# Loguino_mini_v1_2.net
KiCad netlist of a schematic drawn in EAGLE
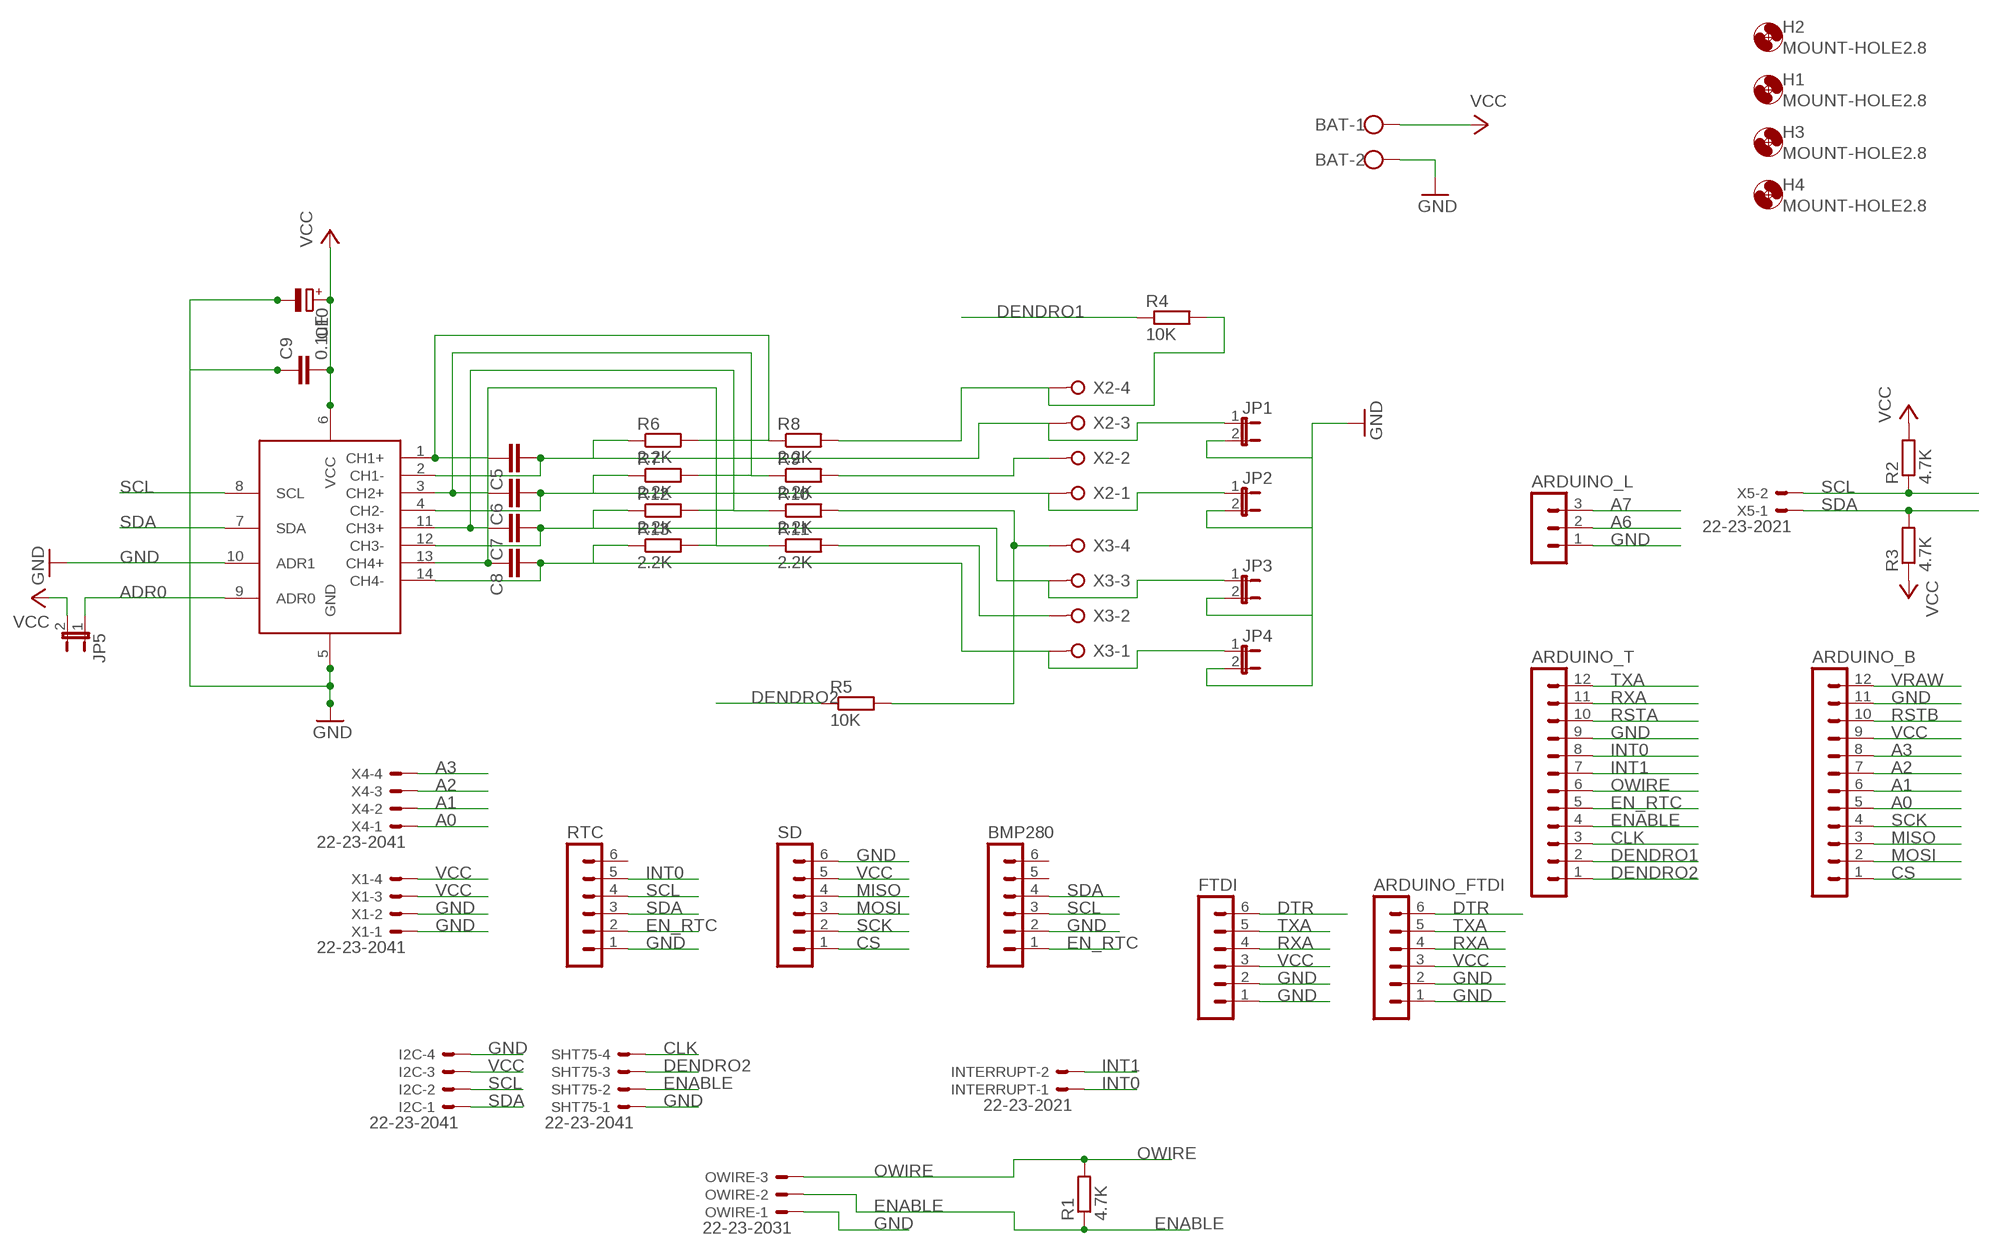
[diagram p0: schematic, sheet 1]

(export (version "E")
  (design (tool "Eeschema 10.0.6"))
  (components
    (comp (ref "ARDUINO_B")
      (value "MA12-1")
      (footprint "eagle-import:MA12-1")
      (libsource (lib "eagle-import") (part "MA12-1"))
    )
    (comp (ref "ARDUINO_FTDI")
      (value "MA06-1")
      (footprint "eagle-import:MA06-1")
      (libsource (lib "eagle-import") (part "MA06-1"))
    )
    (comp (ref "ARDUINO_L")
      (value "MA03-1")
      (footprint "eagle-import:MA03-1")
      (libsource (lib "eagle-import") (part "MA03-1"))
    )
    (comp (ref "ARDUINO_T")
      (value "MA12-1")
      (footprint "eagle-import:MA12-1")
      (libsource (lib "eagle-import") (part "MA12-1"))
    )
    (comp (ref "BAT")
      (value "W237-102")
      (footprint "eagle-import:W237-102")
      (fields (field (name "MPN") "237-102"))
      (libsource (lib "eagle-import") (part "W237-102"))
    )
    (comp (ref "BMP280")
      (value "MA06-1")
      (footprint "eagle-import:MA06-1")
      (libsource (lib "eagle-import") (part "MA06-1"))
    )
    (comp (ref "C5")
      (value "C-EU025-024X044")
      (footprint "eagle-import:C025-024X044")
      (libsource (lib "eagle-import") (part "C-EU025-024X044"))
    )
    (comp (ref "C6")
      (value "C-EU025-024X044")
      (footprint "eagle-import:C025-024X044")
      (libsource (lib "eagle-import") (part "C-EU025-024X044"))
    )
    (comp (ref "C7")
      (value "C-EU025-024X044")
      (footprint "eagle-import:C025-024X044")
      (libsource (lib "eagle-import") (part "C-EU025-024X044"))
    )
    (comp (ref "C8")
      (value "C-EU025-024X044")
      (footprint "eagle-import:C025-024X044")
      (libsource (lib "eagle-import") (part "C-EU025-024X044"))
    )
    (comp (ref "C9")
      (value "0.1uF")
      (footprint "eagle-import:C050-025X075")
      (libsource (lib "eagle-import") (part "C-EU050-025X075"))
    )
    (comp (ref "C10")
      (value "CPOL-EUE2,5-6E")
      (footprint "eagle-import:E2,5-6E")
      (libsource (lib "eagle-import") (part "CPOL-EUE2,5-6E"))
    )
    (comp (ref "FTDI")
      (value "MA06-1")
      (footprint "eagle-import:MA06-1")
      (libsource (lib "eagle-import") (part "MA06-1"))
    )
    (comp (ref "H1")
      (value "MOUNT-HOLE2.8")
      (footprint "eagle-import:2,8")
      (libsource (lib "eagle-import") (part "MOUNT-HOLE2.8"))
    )
    (comp (ref "H2")
      (value "MOUNT-HOLE2.8")
      (footprint "eagle-import:2,8")
      (libsource (lib "eagle-import") (part "MOUNT-HOLE2.8"))
    )
    (comp (ref "H3")
      (value "MOUNT-HOLE2.8")
      (footprint "eagle-import:2,8")
      (libsource (lib "eagle-import") (part "MOUNT-HOLE2.8"))
    )
    (comp (ref "H4")
      (value "MOUNT-HOLE2.8")
      (footprint "eagle-import:2,8")
      (libsource (lib "eagle-import") (part "MOUNT-HOLE2.8"))
    )
    (comp (ref "I2C")
      (value "22-23-2041")
      (footprint "eagle-import:22-23-2041")
      (fields (field (name "MF") "MOLEX"))
      (libsource (lib "eagle-import") (part "22-23-2041"))
    )
    (comp (ref "INTERRUPT")
      (value "22-23-2021")
      (footprint "eagle-import:22-23-2021")
      (fields (field (name "MF") "MOLEX"))
      (libsource (lib "eagle-import") (part "22-23-2021"))
    )
    (comp (ref "JP1")
      (value "JP1E")
      (footprint "eagle-import:JP1")
      (libsource (lib "eagle-import") (part "JP1E"))
    )
    (comp (ref "JP2")
      (value "JP1E")
      (footprint "eagle-import:JP1")
      (libsource (lib "eagle-import") (part "JP1E"))
    )
    (comp (ref "JP3")
      (value "JP1E")
      (footprint "eagle-import:JP1")
      (libsource (lib "eagle-import") (part "JP1E"))
    )
    (comp (ref "JP4")
      (value "JP1E")
      (footprint "eagle-import:JP1")
      (libsource (lib "eagle-import") (part "JP1E"))
    )
    (comp (ref "JP5")
      (value "JP1E")
      (footprint "eagle-import:JP1")
      (libsource (lib "eagle-import") (part "JP1E"))
    )
    (comp (ref "OWIRE")
      (value "22-23-2031")
      (footprint "eagle-import:22-23-2031")
      (fields (field (name "MF") "MOLEX"))
      (libsource (lib "eagle-import") (part "22-23-2031"))
    )
    (comp (ref "R1")
      (value "4.7K")
      (footprint "eagle-import:0204_7")
      (libsource (lib "eagle-import") (part "R-EU_0204/7"))
    )
    (comp (ref "R2")
      (value "4.7K")
      (footprint "eagle-import:0204_7")
      (libsource (lib "eagle-import") (part "R-EU_0204/7"))
    )
    (comp (ref "R3")
      (value "4.7K")
      (footprint "eagle-import:0204_7")
      (libsource (lib "eagle-import") (part "R-EU_0204/7"))
    )
    (comp (ref "R4")
      (value "10K")
      (footprint "eagle-import:0207_10")
      (libsource (lib "eagle-import") (part "resistor_R-EU_0207/10"))
    )
    (comp (ref "R5")
      (value "10K")
      (footprint "eagle-import:0207_10")
      (libsource (lib "eagle-import") (part "resistor_R-EU_0207/10"))
    )
    (comp (ref "R6")
      (value "2.2K")
      (footprint "eagle-import:0207_10")
      (libsource (lib "eagle-import") (part "resistor_R-EU_0207/10"))
    )
    (comp (ref "R7")
      (value "2.2K")
      (footprint "eagle-import:0207_10")
      (libsource (lib "eagle-import") (part "resistor_R-EU_0207/10"))
    )
    (comp (ref "R8")
      (value "2.2K")
      (footprint "eagle-import:0207_10")
      (libsource (lib "eagle-import") (part "resistor_R-EU_0207/10"))
    )
    (comp (ref "R9")
      (value "2.2K")
      (footprint "eagle-import:0207_10")
      (libsource (lib "eagle-import") (part "resistor_R-EU_0207/10"))
    )
    (comp (ref "R10")
      (value "2.2K")
      (footprint "eagle-import:0207_10")
      (libsource (lib "eagle-import") (part "resistor_R-EU_0207/10"))
    )
    (comp (ref "R11")
      (value "2.2K")
      (footprint "eagle-import:0207_10")
      (libsource (lib "eagle-import") (part "resistor_R-EU_0207/10"))
    )
    (comp (ref "R12")
      (value "2.2K")
      (footprint "eagle-import:0207_10")
      (libsource (lib "eagle-import") (part "resistor_R-EU_0207/10"))
    )
    (comp (ref "R13")
      (value "2.2K")
      (footprint "eagle-import:0207_10")
      (libsource (lib "eagle-import") (part "resistor_R-EU_0207/10"))
    )
    (comp (ref "RTC")
      (value "MA06-1")
      (footprint "eagle-import:MA06-1")
      (libsource (lib "eagle-import") (part "MA06-1"))
    )
    (comp (ref "SD")
      (value "MA06-1")
      (footprint "eagle-import:MA06-1")
      (libsource (lib "eagle-import") (part "MA06-1"))
    )
    (comp (ref "SHT75")
      (value "22-23-2041")
      (footprint "eagle-import:22-23-2041")
      (fields (field (name "MF") "MOLEX"))
      (libsource (lib "eagle-import") (part "22-23-2041"))
    )
    (comp (ref "U$2")
      (value "MCP342")
      (footprint "eagle-import:SO14")
      (libsource (lib "eagle-import") (part "MCP342"))
    )
    (comp (ref "X1")
      (value "22-23-2041")
      (footprint "eagle-import:22-23-2041")
      (fields (field (name "MF") "MOLEX"))
      (libsource (lib "eagle-import") (part "22-23-2041"))
    )
    (comp (ref "X2")
      (value "W237-04P")
      (footprint "eagle-import:W237-4P")
      (libsource (lib "eagle-import") (part "W237-04P"))
    )
    (comp (ref "X3")
      (value "W237-04P")
      (footprint "eagle-import:W237-4P")
      (libsource (lib "eagle-import") (part "W237-04P"))
    )
    (comp (ref "X4")
      (value "22-23-2041")
      (footprint "eagle-import:22-23-2041")
      (fields (field (name "MF") "MOLEX"))
      (libsource (lib "eagle-import") (part "22-23-2041"))
    )
    (comp (ref "X5")
      (value "22-23-2021")
      (footprint "eagle-import:22-23-2021")
      (fields (field (name "MF") "MOLEX"))
      (libsource (lib "eagle-import") (part "22-23-2021"))
    )
  )
  (nets
    (net (code "1") (name "/A0") (class "Default")
      (node (ref "ARDUINO_B") (pin "5") (pinfunction "5_5") (pintype "passive"))
      (node (ref "X4") (pin "1") (pinfunction "S_1") (pintype "passive"))
    )
    (net (code "2") (name "/A1") (class "Default")
      (node (ref "ARDUINO_B") (pin "6") (pinfunction "6_6") (pintype "passive"))
      (node (ref "X4") (pin "2") (pinfunction "S_2") (pintype "passive"))
    )
    (net (code "3") (name "/A2") (class "Default")
      (node (ref "ARDUINO_B") (pin "7") (pinfunction "7_7") (pintype "passive"))
      (node (ref "X4") (pin "3") (pinfunction "S_3") (pintype "passive"))
    )
    (net (code "4") (name "/A3") (class "Default")
      (node (ref "ARDUINO_B") (pin "8") (pinfunction "8_8") (pintype "passive"))
      (node (ref "X4") (pin "4") (pinfunction "S_4") (pintype "passive"))
    )
    (net (code "5") (name "/A6") (class "Default")
      (node (ref "ARDUINO_L") (pin "2") (pinfunction "2_2") (pintype "passive"))
    )
    (net (code "6") (name "/A7") (class "Default")
      (node (ref "ARDUINO_L") (pin "3") (pinfunction "3_3") (pintype "passive"))
    )
    (net (code "7") (name "/ADR0") (class "Default")
      (node (ref "JP5") (pin "1") (pinfunction "1_1") (pintype "passive"))
      (node (ref "U$2") (pin "9") (pinfunction "ADR0_9") (pintype "bidirectional"))
    )
    (net (code "8") (name "/CLK") (class "Default")
      (node (ref "ARDUINO_T") (pin "3") (pinfunction "3_3") (pintype "passive"))
      (node (ref "SHT75") (pin "4") (pinfunction "S_4") (pintype "passive"))
    )
    (net (code "9") (name "/CS") (class "Default")
      (node (ref "ARDUINO_B") (pin "1") (pinfunction "1_1") (pintype "passive"))
      (node (ref "SD") (pin "1") (pinfunction "1_1") (pintype "passive"))
    )
    (net (code "10") (name "/DENDRO1") (class "Default")
      (node (ref "ARDUINO_T") (pin "2") (pinfunction "2_2") (pintype "passive"))
      (node (ref "R4") (pin "1") (pinfunction "1_1") (pintype "passive"))
    )
    (net (code "11") (name "/DENDRO2") (class "Default")
      (node (ref "ARDUINO_T") (pin "1") (pinfunction "1_1") (pintype "passive"))
      (node (ref "R5") (pin "1") (pinfunction "1_1") (pintype "passive"))
      (node (ref "SHT75") (pin "3") (pinfunction "S_3") (pintype "passive"))
    )
    (net (code "12") (name "/DTR") (class "Default")
      (node (ref "ARDUINO_FTDI") (pin "6") (pinfunction "6_6") (pintype "passive"))
      (node (ref "FTDI") (pin "6") (pinfunction "6_6") (pintype "passive"))
    )
    (net (code "13") (name "/ENABLE") (class "Default")
      (node (ref "ARDUINO_T") (pin "4") (pinfunction "4_4") (pintype "passive"))
      (node (ref "OWIRE") (pin "2") (pinfunction "S_2") (pintype "passive"))
      (node (ref "R1") (pin "1") (pinfunction "1_1") (pintype "passive"))
      (node (ref "SHT75") (pin "2") (pinfunction "S_2") (pintype "passive"))
    )
    (net (code "14") (name "/EN_RTC") (class "Default")
      (node (ref "ARDUINO_T") (pin "5") (pinfunction "5_5") (pintype "passive"))
      (node (ref "BMP280") (pin "1") (pinfunction "1_1") (pintype "passive"))
      (node (ref "RTC") (pin "2") (pinfunction "2_2") (pintype "passive"))
    )
    (net (code "15") (name "/INT0") (class "Default")
      (node (ref "ARDUINO_T") (pin "8") (pinfunction "8_8") (pintype "passive"))
      (node (ref "INTERRUPT") (pin "1") (pinfunction "S_1") (pintype "passive"))
      (node (ref "RTC") (pin "5") (pinfunction "5_5") (pintype "passive"))
    )
    (net (code "16") (name "/INT1") (class "Default")
      (node (ref "ARDUINO_T") (pin "7") (pinfunction "7_7") (pintype "passive"))
      (node (ref "INTERRUPT") (pin "2") (pinfunction "S_2") (pintype "passive"))
    )
    (net (code "17") (name "/MISO") (class "Default")
      (node (ref "ARDUINO_B") (pin "3") (pinfunction "3_3") (pintype "passive"))
      (node (ref "SD") (pin "4") (pinfunction "4_4") (pintype "passive"))
    )
    (net (code "18") (name "/MOSI") (class "Default")
      (node (ref "ARDUINO_B") (pin "2") (pinfunction "2_2") (pintype "passive"))
      (node (ref "SD") (pin "3") (pinfunction "3_3") (pintype "passive"))
    )
    (net (code "19") (name "/OWIRE") (class "Default")
      (node (ref "ARDUINO_T") (pin "6") (pinfunction "6_6") (pintype "passive"))
      (node (ref "OWIRE") (pin "3") (pinfunction "S_3") (pintype "passive"))
      (node (ref "R1") (pin "2") (pinfunction "2_2") (pintype "passive"))
    )
    (net (code "20") (name "/RSTA") (class "Default")
      (node (ref "ARDUINO_T") (pin "10") (pinfunction "10_10") (pintype "passive"))
    )
    (net (code "21") (name "/RSTB") (class "Default")
      (node (ref "ARDUINO_B") (pin "10") (pinfunction "10_10") (pintype "passive"))
    )
    (net (code "22") (name "/RXA") (class "Default")
      (node (ref "ARDUINO_FTDI") (pin "4") (pinfunction "4_4") (pintype "passive"))
      (node (ref "ARDUINO_T") (pin "11") (pinfunction "11_11") (pintype "passive"))
      (node (ref "FTDI") (pin "4") (pinfunction "4_4") (pintype "passive"))
    )
    (net (code "23") (name "/SCK") (class "Default")
      (node (ref "ARDUINO_B") (pin "4") (pinfunction "4_4") (pintype "passive"))
      (node (ref "SD") (pin "2") (pinfunction "2_2") (pintype "passive"))
    )
    (net (code "24") (name "/SCL") (class "Default")
      (node (ref "BMP280") (pin "3") (pinfunction "3_3") (pintype "passive"))
      (node (ref "I2C") (pin "2") (pinfunction "S_2") (pintype "passive"))
      (node (ref "R2") (pin "1") (pinfunction "1_1") (pintype "passive"))
      (node (ref "RTC") (pin "4") (pinfunction "4_4") (pintype "passive"))
      (node (ref "U$2") (pin "8") (pinfunction "SCL_8") (pintype "bidirectional"))
      (node (ref "X5") (pin "2") (pinfunction "S_2") (pintype "passive"))
    )
    (net (code "25") (name "/SDA") (class "Default")
      (node (ref "BMP280") (pin "4") (pinfunction "4_4") (pintype "passive"))
      (node (ref "I2C") (pin "1") (pinfunction "S_1") (pintype "passive"))
      (node (ref "R3") (pin "2") (pinfunction "2_2") (pintype "passive"))
      (node (ref "RTC") (pin "3") (pinfunction "3_3") (pintype "passive"))
      (node (ref "U$2") (pin "7") (pinfunction "SDA_7") (pintype "bidirectional"))
      (node (ref "X5") (pin "1") (pinfunction "S_1") (pintype "passive"))
    )
    (net (code "26") (name "/TXA") (class "Default")
      (node (ref "ARDUINO_FTDI") (pin "5") (pinfunction "5_5") (pintype "passive"))
      (node (ref "ARDUINO_T") (pin "12") (pinfunction "12_12") (pintype "passive"))
      (node (ref "FTDI") (pin "5") (pinfunction "5_5") (pintype "passive"))
    )
    (net (code "27") (name "/VRAW") (class "Default")
      (node (ref "ARDUINO_B") (pin "12") (pinfunction "12_12") (pintype "passive"))
    )
    (net (code "28") (name "GND") (class "Default")
      (node (ref "ARDUINO_B") (pin "11") (pinfunction "11_11") (pintype "passive"))
      (node (ref "ARDUINO_FTDI") (pin "1") (pinfunction "1_1") (pintype "passive"))
      (node (ref "ARDUINO_FTDI") (pin "2") (pinfunction "2_2") (pintype "passive"))
      (node (ref "ARDUINO_L") (pin "1") (pinfunction "1_1") (pintype "passive"))
      (node (ref "ARDUINO_T") (pin "9") (pinfunction "9_9") (pintype "passive"))
      (node (ref "BAT") (pin "2") (pinfunction "KL_2") (pintype "passive"))
      (node (ref "BMP280") (pin "2") (pinfunction "2_2") (pintype "passive"))
      (node (ref "C10") (pin "-") (pinfunction "-_-") (pintype "passive"))
      (node (ref "C9") (pin "1") (pinfunction "1_1") (pintype "passive"))
      (node (ref "FTDI") (pin "1") (pinfunction "1_1") (pintype "passive"))
      (node (ref "FTDI") (pin "2") (pinfunction "2_2") (pintype "passive"))
      (node (ref "I2C") (pin "4") (pinfunction "S_4") (pintype "passive"))
      (node (ref "JP1") (pin "2") (pinfunction "2_2") (pintype "passive"))
      (node (ref "JP2") (pin "2") (pinfunction "2_2") (pintype "passive"))
      (node (ref "JP3") (pin "2") (pinfunction "2_2") (pintype "passive"))
      (node (ref "JP4") (pin "2") (pinfunction "2_2") (pintype "passive"))
      (node (ref "OWIRE") (pin "1") (pinfunction "S_1") (pintype "passive"))
      (node (ref "RTC") (pin "1") (pinfunction "1_1") (pintype "passive"))
      (node (ref "SD") (pin "6") (pinfunction "6_6") (pintype "passive"))
      (node (ref "SHT75") (pin "1") (pinfunction "S_1") (pintype "passive"))
      (node (ref "U$2") (pin "10") (pinfunction "ADR1_10") (pintype "bidirectional"))
      (node (ref "U$2") (pin "5") (pinfunction "GND_5") (pintype "bidirectional"))
      (node (ref "X1") (pin "1") (pinfunction "S_1") (pintype "passive"))
      (node (ref "X1") (pin "2") (pinfunction "S_2") (pintype "passive"))
    )
    (net (code "29") (name "Net-(U$2-CH1+)") (class "Default")
      (node (ref "C5") (pin "1") (pinfunction "1_1") (pintype "passive"))
      (node (ref "R6") (pin "2") (pinfunction "2_2") (pintype "passive"))
      (node (ref "R8") (pin "1") (pinfunction "1_1") (pintype "passive"))
      (node (ref "U$2") (pin "1") (pinfunction "CH1+_1") (pintype "bidirectional"))
    )
    (net (code "30") (name "Net-(U$2-CH1-)") (class "Default")
      (node (ref "C5") (pin "2") (pinfunction "2_2") (pintype "passive"))
      (node (ref "JP1") (pin "1") (pinfunction "1_1") (pintype "passive"))
      (node (ref "R6") (pin "1") (pinfunction "1_1") (pintype "passive"))
      (node (ref "U$2") (pin "2") (pinfunction "CH1-_2") (pintype "bidirectional"))
      (node (ref "X2") (pin "3") (pinfunction "KL_3") (pintype "passive"))
    )
    (net (code "31") (name "Net-(U$2-CH2+)") (class "Default")
      (node (ref "C6") (pin "1") (pinfunction "1_1") (pintype "passive"))
      (node (ref "R7") (pin "2") (pinfunction "2_2") (pintype "passive"))
      (node (ref "R9") (pin "1") (pinfunction "1_1") (pintype "passive"))
      (node (ref "U$2") (pin "3") (pinfunction "CH2+_3") (pintype "bidirectional"))
    )
    (net (code "32") (name "Net-(U$2-CH2-)") (class "Default")
      (node (ref "C6") (pin "2") (pinfunction "2_2") (pintype "passive"))
      (node (ref "JP2") (pin "1") (pinfunction "1_1") (pintype "passive"))
      (node (ref "R7") (pin "1") (pinfunction "1_1") (pintype "passive"))
      (node (ref "U$2") (pin "4") (pinfunction "CH2-_4") (pintype "bidirectional"))
      (node (ref "X2") (pin "1") (pinfunction "KL_1") (pintype "passive"))
    )
    (net (code "33") (name "Net-(U$2-CH3+)") (class "Default")
      (node (ref "C7") (pin "1") (pinfunction "1_1") (pintype "passive"))
      (node (ref "R10") (pin "1") (pinfunction "1_1") (pintype "passive"))
      (node (ref "R12") (pin "2") (pinfunction "2_2") (pintype "passive"))
      (node (ref "U$2") (pin "11") (pinfunction "CH3+_11") (pintype "bidirectional"))
    )
    (net (code "34") (name "Net-(U$2-CH3-)") (class "Default")
      (node (ref "C7") (pin "2") (pinfunction "2_2") (pintype "passive"))
      (node (ref "JP3") (pin "1") (pinfunction "1_1") (pintype "passive"))
      (node (ref "R12") (pin "1") (pinfunction "1_1") (pintype "passive"))
      (node (ref "U$2") (pin "12") (pinfunction "CH3-_12") (pintype "bidirectional"))
      (node (ref "X3") (pin "3") (pinfunction "KL_3") (pintype "passive"))
    )
    (net (code "35") (name "Net-(U$2-CH4+)") (class "Default")
      (node (ref "C8") (pin "1") (pinfunction "1_1") (pintype "passive"))
      (node (ref "R11") (pin "1") (pinfunction "1_1") (pintype "passive"))
      (node (ref "R13") (pin "2") (pinfunction "2_2") (pintype "passive"))
      (node (ref "U$2") (pin "13") (pinfunction "CH4+_13") (pintype "bidirectional"))
    )
    (net (code "36") (name "Net-(U$2-CH4-)") (class "Default")
      (node (ref "C8") (pin "2") (pinfunction "2_2") (pintype "passive"))
      (node (ref "JP4") (pin "1") (pinfunction "1_1") (pintype "passive"))
      (node (ref "R13") (pin "1") (pinfunction "1_1") (pintype "passive"))
      (node (ref "U$2") (pin "14") (pinfunction "CH4-_14") (pintype "bidirectional"))
      (node (ref "X3") (pin "1") (pinfunction "KL_1") (pintype "passive"))
    )
    (net (code "37") (name "Net-(X2B-KL)") (class "Default")
      (node (ref "R9") (pin "2") (pinfunction "2_2") (pintype "passive"))
      (node (ref "X2") (pin "2") (pinfunction "KL_2") (pintype "passive"))
    )
    (net (code "38") (name "Net-(X2D-KL)") (class "Default")
      (node (ref "R4") (pin "2") (pinfunction "2_2") (pintype "passive"))
      (node (ref "R8") (pin "2") (pinfunction "2_2") (pintype "passive"))
      (node (ref "X2") (pin "4") (pinfunction "KL_4") (pintype "passive"))
    )
    (net (code "39") (name "Net-(X3B-KL)") (class "Default")
      (node (ref "R11") (pin "2") (pinfunction "2_2") (pintype "passive"))
      (node (ref "X3") (pin "2") (pinfunction "KL_2") (pintype "passive"))
    )
    (net (code "40") (name "Net-(X3D-KL)") (class "Default")
      (node (ref "R10") (pin "2") (pinfunction "2_2") (pintype "passive"))
      (node (ref "R5") (pin "2") (pinfunction "2_2") (pintype "passive"))
      (node (ref "X3") (pin "4") (pinfunction "KL_4") (pintype "passive"))
    )
    (net (code "41") (name "VCC") (class "Default")
      (node (ref "ARDUINO_B") (pin "9") (pinfunction "9_9") (pintype "passive"))
      (node (ref "ARDUINO_FTDI") (pin "3") (pinfunction "3_3") (pintype "passive"))
      (node (ref "BAT") (pin "1") (pinfunction "KL_1") (pintype "passive"))
      (node (ref "C10") (pin "+") (pinfunction "+_+") (pintype "passive"))
      (node (ref "C9") (pin "2") (pinfunction "2_2") (pintype "passive"))
      (node (ref "FTDI") (pin "3") (pinfunction "3_3") (pintype "passive"))
      (node (ref "I2C") (pin "3") (pinfunction "S_3") (pintype "passive"))
      (node (ref "JP5") (pin "2") (pinfunction "2_2") (pintype "passive"))
      (node (ref "R2") (pin "2") (pinfunction "2_2") (pintype "passive"))
      (node (ref "R3") (pin "1") (pinfunction "1_1") (pintype "passive"))
      (node (ref "SD") (pin "5") (pinfunction "5_5") (pintype "passive"))
      (node (ref "U$2") (pin "6") (pinfunction "VCC_6") (pintype "bidirectional"))
      (node (ref "X1") (pin "3") (pinfunction "S_3") (pintype "passive"))
      (node (ref "X1") (pin "4") (pinfunction "S_4") (pintype "passive"))
    )
    (net (code "42") (name "unconnected-(BMP280-Pad5)") (class "Default")
      (node (ref "BMP280") (pin "5") (pinfunction "5_5") (pintype "passive"))
    )
    (net (code "43") (name "unconnected-(BMP280-Pad6)") (class "Default")
      (node (ref "BMP280") (pin "6") (pinfunction "6_6") (pintype "passive"))
    )
    (net (code "44") (name "unconnected-(RTC-Pad6)") (class "Default")
      (node (ref "RTC") (pin "6") (pinfunction "6_6") (pintype "passive"))
    )
  )
)
